# Adafruit_LM3671_Buck.net
KiCad netlist of a schematic drawn in EAGLE
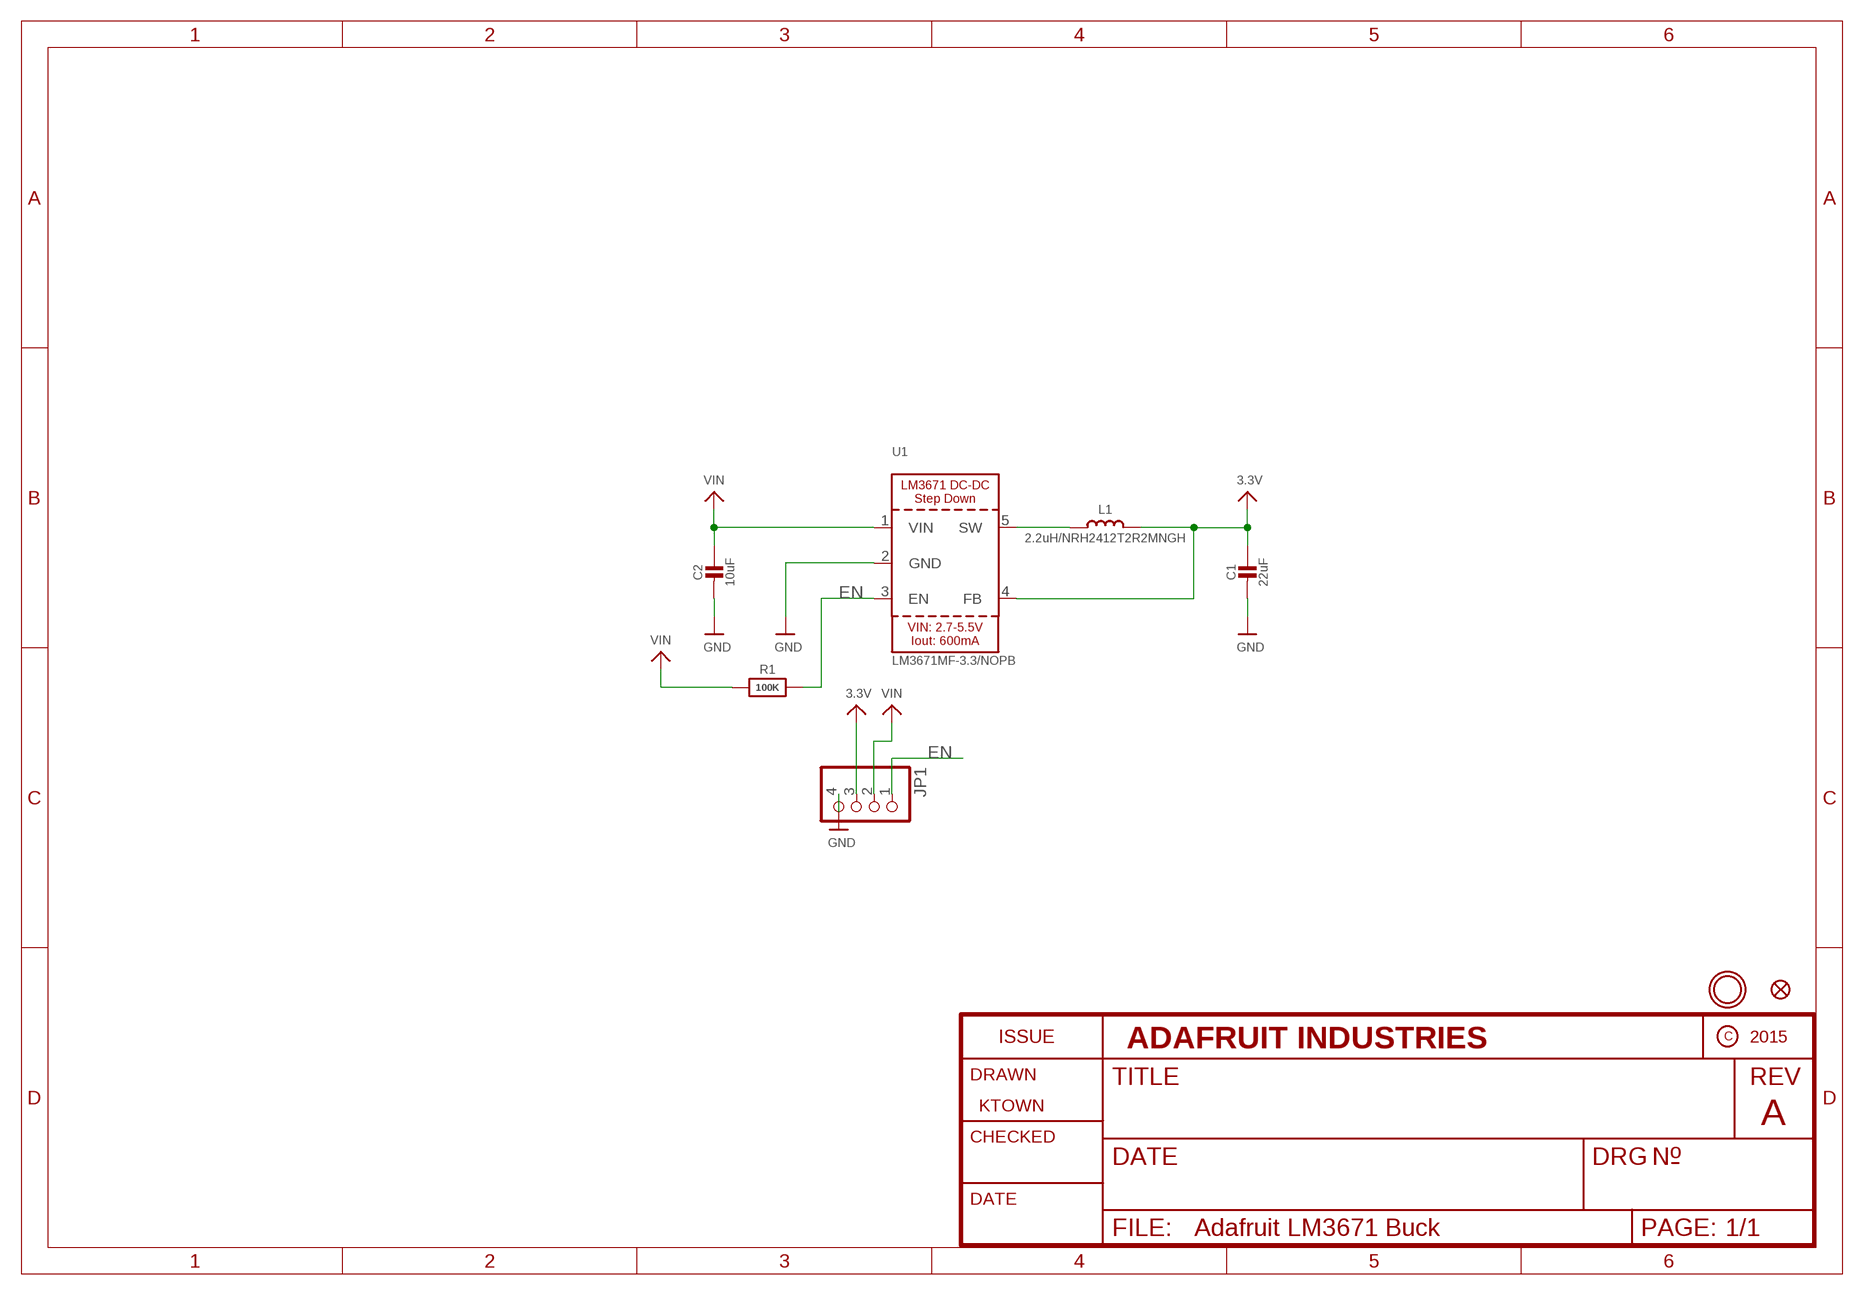
[diagram p0: schematic, sheet 1]

(export (version "E")
  (design (tool "Eeschema 10.0.6"))
  (components
    (comp (ref "C1")
      (value "22uF")
      (footprint "eagle-import:0805-NO")
      (libsource (lib "eagle-import") (part "CAP_CERAMIC0805-NOOUTLINE"))
    )
    (comp (ref "C2")
      (value "10uF")
      (footprint "eagle-import:0805-NO")
      (libsource (lib "eagle-import") (part "CAP_CERAMIC0805-NOOUTLINE"))
    )
    (comp (ref "FID1")
      (value "FIDUCIAL\"\"")
      (footprint "eagle-import:FIDUCIAL_1MM")
      (libsource (lib "eagle-import") (part "FIDUCIAL{dblquote}{dblquote}"))
    )
    (comp (ref "JP1")
      (value "HEADER-1X4ROUND")
      (footprint "eagle-import:1X04_ROUND")
      (libsource (lib "eagle-import") (part "HEADER-1X4ROUND"))
    )
    (comp (ref "L1")
      (value "2.2uH/NRH2412T2R2MNGH")
      (footprint "eagle-import:INDUCTOR_TAIYOYUDEN_NRH2412T")
      (libsource (lib "eagle-import") (part "INDUCTORNRH2412T"))
    )
    (comp (ref "R1")
      (value "100K")
      (footprint "eagle-import:0805-NO")
      (libsource (lib "eagle-import") (part "RESISTOR0805_NOOUTLINE"))
    )
    (comp (ref "U$9")
      (value "MOUNTINGHOLE2.5")
      (footprint "eagle-import:MOUNTINGHOLE_2.5_PLATED")
      (libsource (lib "eagle-import") (part "MOUNTINGHOLE2.5"))
    )
    (comp (ref "U1")
      (value "LM3671MF-3.3/NOPB")
      (footprint "eagle-import:SOT23-5")
      (libsource (lib "eagle-import") (part "VREG_LM3671"))
    )
  )
  (nets
    (net (code "1") (name "/EN") (class "Default")
      (node (ref "JP1") (pin "1") (pinfunction "1_1") (pintype "passive"))
      (node (ref "R1") (pin "2") (pinfunction "2_2") (pintype "passive"))
      (node (ref "U1") (pin "3") (pinfunction "EN_3") (pintype "input"))
    )
    (net (code "2") (name "3.3V") (class "Default")
      (node (ref "C1") (pin "1") (pinfunction "1_1") (pintype "passive"))
      (node (ref "JP1") (pin "3") (pinfunction "3_3") (pintype "passive"))
      (node (ref "L1") (pin "2") (pinfunction "2_2") (pintype "passive"))
      (node (ref "U1") (pin "4") (pinfunction "FB_4") (pintype "power_in"))
    )
    (net (code "3") (name "GND") (class "Default")
      (node (ref "C1") (pin "2") (pinfunction "2_2") (pintype "passive"))
      (node (ref "C2") (pin "2") (pinfunction "2_2") (pintype "passive"))
      (node (ref "JP1") (pin "4") (pinfunction "4_4") (pintype "passive"))
      (node (ref "U1") (pin "2") (pinfunction "GND_2") (pintype "power_in"))
    )
    (net (code "4") (name "Net-(U1-SW)") (class "Default")
      (node (ref "L1") (pin "1") (pinfunction "1_1") (pintype "passive"))
      (node (ref "U1") (pin "5") (pinfunction "SW_5") (pintype "output"))
    )
    (net (code "5") (name "VIN") (class "Default")
      (node (ref "C2") (pin "1") (pinfunction "1_1") (pintype "passive"))
      (node (ref "JP1") (pin "2") (pinfunction "2_2") (pintype "passive"))
      (node (ref "R1") (pin "1") (pinfunction "1_1") (pintype "passive"))
      (node (ref "U1") (pin "1") (pinfunction "VIN_1") (pintype "power_in"))
    )
  )
)
